# konashi-mini.net
KiCad netlist of a schematic drawn in EAGLE
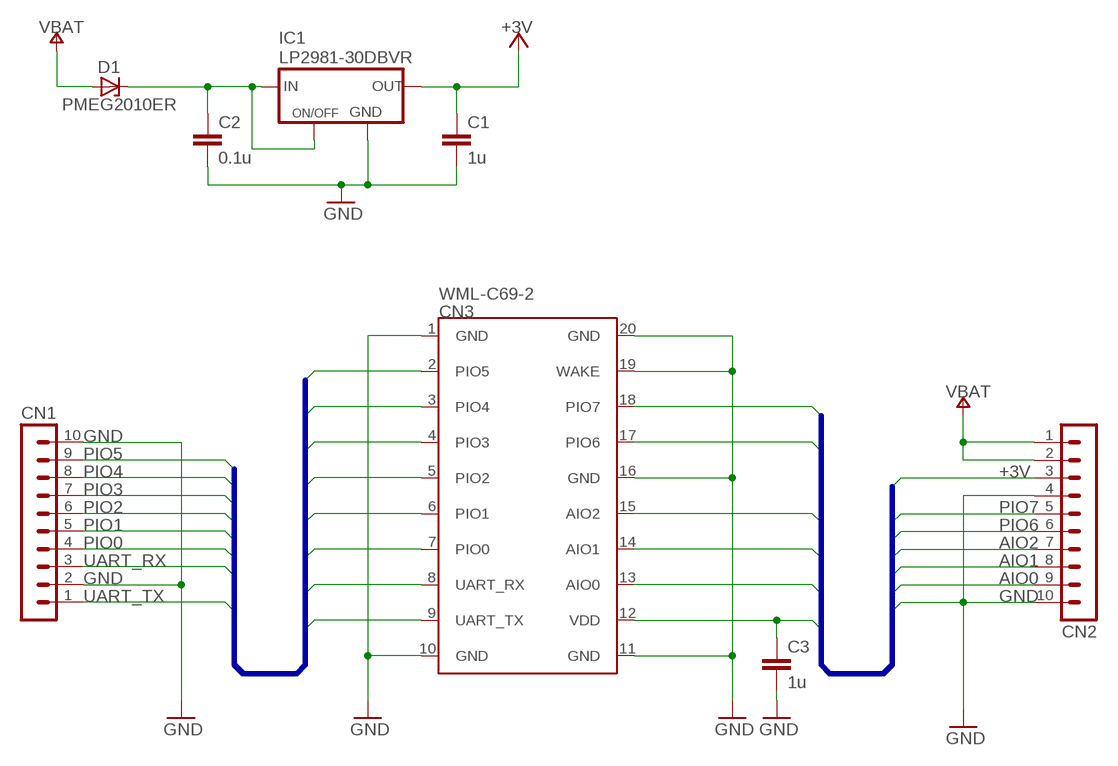
[diagram p0: schematic, sheet 1]

(export (version "E")
  (design (tool "Eeschema 10.0.6"))
  (components
    (comp (ref "C1")
      (value "1u")
      (footprint "eagle-import:C0603")
      (libsource (lib "eagle-import") (part "C-EUC0603"))
    )
    (comp (ref "C2")
      (value "0.1u")
      (footprint "eagle-import:C0603")
      (libsource (lib "eagle-import") (part "C-EUC0603"))
    )
    (comp (ref "C3")
      (value "1u")
      (footprint "eagle-import:C0603")
      (libsource (lib "eagle-import") (part "C-EUC0603"))
    )
    (comp (ref "CN1")
      (value "MA10-1_LARGE")
      (footprint "eagle-import:MA10-1_LARGE")
      (libsource (lib "eagle-import") (part "MA10-1_LARGE"))
    )
    (comp (ref "CN2")
      (value "MA10-1_LARGE")
      (footprint "eagle-import:MA10-1_LARGE")
      (libsource (lib "eagle-import") (part "MA10-1_LARGE"))
    )
    (comp (ref "CN3")
      (value "WML-C69-2")
      (footprint "eagle-import:WML-C69")
      (libsource (lib "eagle-import") (part "WML-C69-2"))
    )
    (comp (ref "D1")
      (value "PMEG2010ER")
      (footprint "eagle-import:SOD123-W")
      (libsource (lib "eagle-import") (part "PMEG2010ER"))
    )
    (comp (ref "IC1")
      (value "LP2981-30DBVR")
      (footprint "eagle-import:SOT-23")
      (libsource (lib "eagle-import") (part "LP2981-30DBVR"))
    )
  )
  (nets
    (net (code "1") (name "+3V") (class "Default")
      (node (ref "C1") (pin "1") (pinfunction "1_1") (pintype "passive"))
      (node (ref "C3") (pin "1") (pinfunction "1_1") (pintype "passive"))
      (node (ref "CN2") (pin "3") (pinfunction "3_3") (pintype "passive"))
      (node (ref "CN3") (pin "12") (pinfunction "VDD_12") (pintype "bidirectional"))
      (node (ref "IC1") (pin "5") (pinfunction "OUT_5") (pintype "passive"))
    )
    (net (code "2") (name "/AIO0") (class "Default")
      (node (ref "CN2") (pin "9") (pinfunction "9_9") (pintype "passive"))
      (node (ref "CN3") (pin "13") (pinfunction "AIO0_13") (pintype "bidirectional"))
    )
    (net (code "3") (name "/AIO1") (class "Default")
      (node (ref "CN2") (pin "8") (pinfunction "8_8") (pintype "passive"))
      (node (ref "CN3") (pin "14") (pinfunction "AIO1_14") (pintype "bidirectional"))
    )
    (net (code "4") (name "/AIO2") (class "Default")
      (node (ref "CN2") (pin "7") (pinfunction "7_7") (pintype "passive"))
      (node (ref "CN3") (pin "15") (pinfunction "AIO2_15") (pintype "bidirectional"))
    )
    (net (code "5") (name "/PIO0") (class "Default")
      (node (ref "CN1") (pin "4") (pinfunction "4_4") (pintype "passive"))
      (node (ref "CN3") (pin "7") (pinfunction "PIO0_7") (pintype "bidirectional"))
    )
    (net (code "6") (name "/PIO1") (class "Default")
      (node (ref "CN1") (pin "5") (pinfunction "5_5") (pintype "passive"))
      (node (ref "CN3") (pin "6") (pinfunction "PIO1_6") (pintype "bidirectional"))
    )
    (net (code "7") (name "/PIO2") (class "Default")
      (node (ref "CN1") (pin "6") (pinfunction "6_6") (pintype "passive"))
      (node (ref "CN3") (pin "5") (pinfunction "PIO2_5") (pintype "bidirectional"))
    )
    (net (code "8") (name "/PIO3") (class "Default")
      (node (ref "CN1") (pin "7") (pinfunction "7_7") (pintype "passive"))
      (node (ref "CN3") (pin "4") (pinfunction "PIO3_4") (pintype "bidirectional"))
    )
    (net (code "9") (name "/PIO4") (class "Default")
      (node (ref "CN1") (pin "8") (pinfunction "8_8") (pintype "passive"))
      (node (ref "CN3") (pin "3") (pinfunction "PIO4_3") (pintype "bidirectional"))
    )
    (net (code "10") (name "/PIO5") (class "Default")
      (node (ref "CN1") (pin "9") (pinfunction "9_9") (pintype "passive"))
      (node (ref "CN3") (pin "2") (pinfunction "PIO5_2") (pintype "bidirectional"))
    )
    (net (code "11") (name "/PIO6") (class "Default")
      (node (ref "CN2") (pin "6") (pinfunction "6_6") (pintype "passive"))
      (node (ref "CN3") (pin "17") (pinfunction "PIO6_17") (pintype "bidirectional"))
    )
    (net (code "12") (name "/PIO7") (class "Default")
      (node (ref "CN2") (pin "5") (pinfunction "5_5") (pintype "passive"))
      (node (ref "CN3") (pin "18") (pinfunction "PIO7_18") (pintype "bidirectional"))
    )
    (net (code "13") (name "/UART_RX") (class "Default")
      (node (ref "CN1") (pin "3") (pinfunction "3_3") (pintype "passive"))
      (node (ref "CN3") (pin "8") (pinfunction "UART_RX_8") (pintype "bidirectional"))
    )
    (net (code "14") (name "/UART_TX") (class "Default")
      (node (ref "CN1") (pin "1") (pinfunction "1_1") (pintype "passive"))
      (node (ref "CN3") (pin "9") (pinfunction "UART_TX_9") (pintype "bidirectional"))
    )
    (net (code "15") (name "GND") (class "Default")
      (node (ref "C1") (pin "2") (pinfunction "2_2") (pintype "passive"))
      (node (ref "C2") (pin "2") (pinfunction "2_2") (pintype "passive"))
      (node (ref "C3") (pin "2") (pinfunction "2_2") (pintype "passive"))
      (node (ref "CN1") (pin "10") (pinfunction "10_10") (pintype "passive"))
      (node (ref "CN1") (pin "2") (pinfunction "2_2") (pintype "passive"))
      (node (ref "CN2") (pin "10") (pinfunction "10_10") (pintype "passive"))
      (node (ref "CN2") (pin "4") (pinfunction "4_4") (pintype "passive"))
      (node (ref "CN3") (pin "1") (pinfunction "GND_1") (pintype "bidirectional"))
      (node (ref "CN3") (pin "10") (pinfunction "GND_10") (pintype "bidirectional"))
      (node (ref "CN3") (pin "11") (pinfunction "GND_11") (pintype "bidirectional"))
      (node (ref "CN3") (pin "16") (pinfunction "GND_16") (pintype "bidirectional"))
      (node (ref "CN3") (pin "19") (pinfunction "WAKE_19") (pintype "bidirectional"))
      (node (ref "CN3") (pin "20") (pinfunction "GND_20") (pintype "bidirectional"))
      (node (ref "IC1") (pin "2") (pinfunction "GND_2") (pintype "input"))
    )
    (net (code "16") (name "Net-(D1-C)") (class "Default")
      (node (ref "C2") (pin "1") (pinfunction "1_1") (pintype "passive"))
      (node (ref "D1") (pin "K") (pinfunction "C_K") (pintype "passive"))
      (node (ref "IC1") (pin "1") (pinfunction "IN_1") (pintype "input"))
      (node (ref "IC1") (pin "3") (pinfunction "ON/OFF_3") (pintype "bidirectional"))
    )
    (net (code "17") (name "VBAT") (class "Default")
      (node (ref "CN2") (pin "1") (pinfunction "1_1") (pintype "passive"))
      (node (ref "CN2") (pin "2") (pinfunction "2_2") (pintype "passive"))
      (node (ref "D1") (pin "A") (pinfunction "A_A") (pintype "passive"))
    )
  )
)
